# Motorsteuerung_V4.net
KiCad netlist of a schematic drawn in Altium Designer
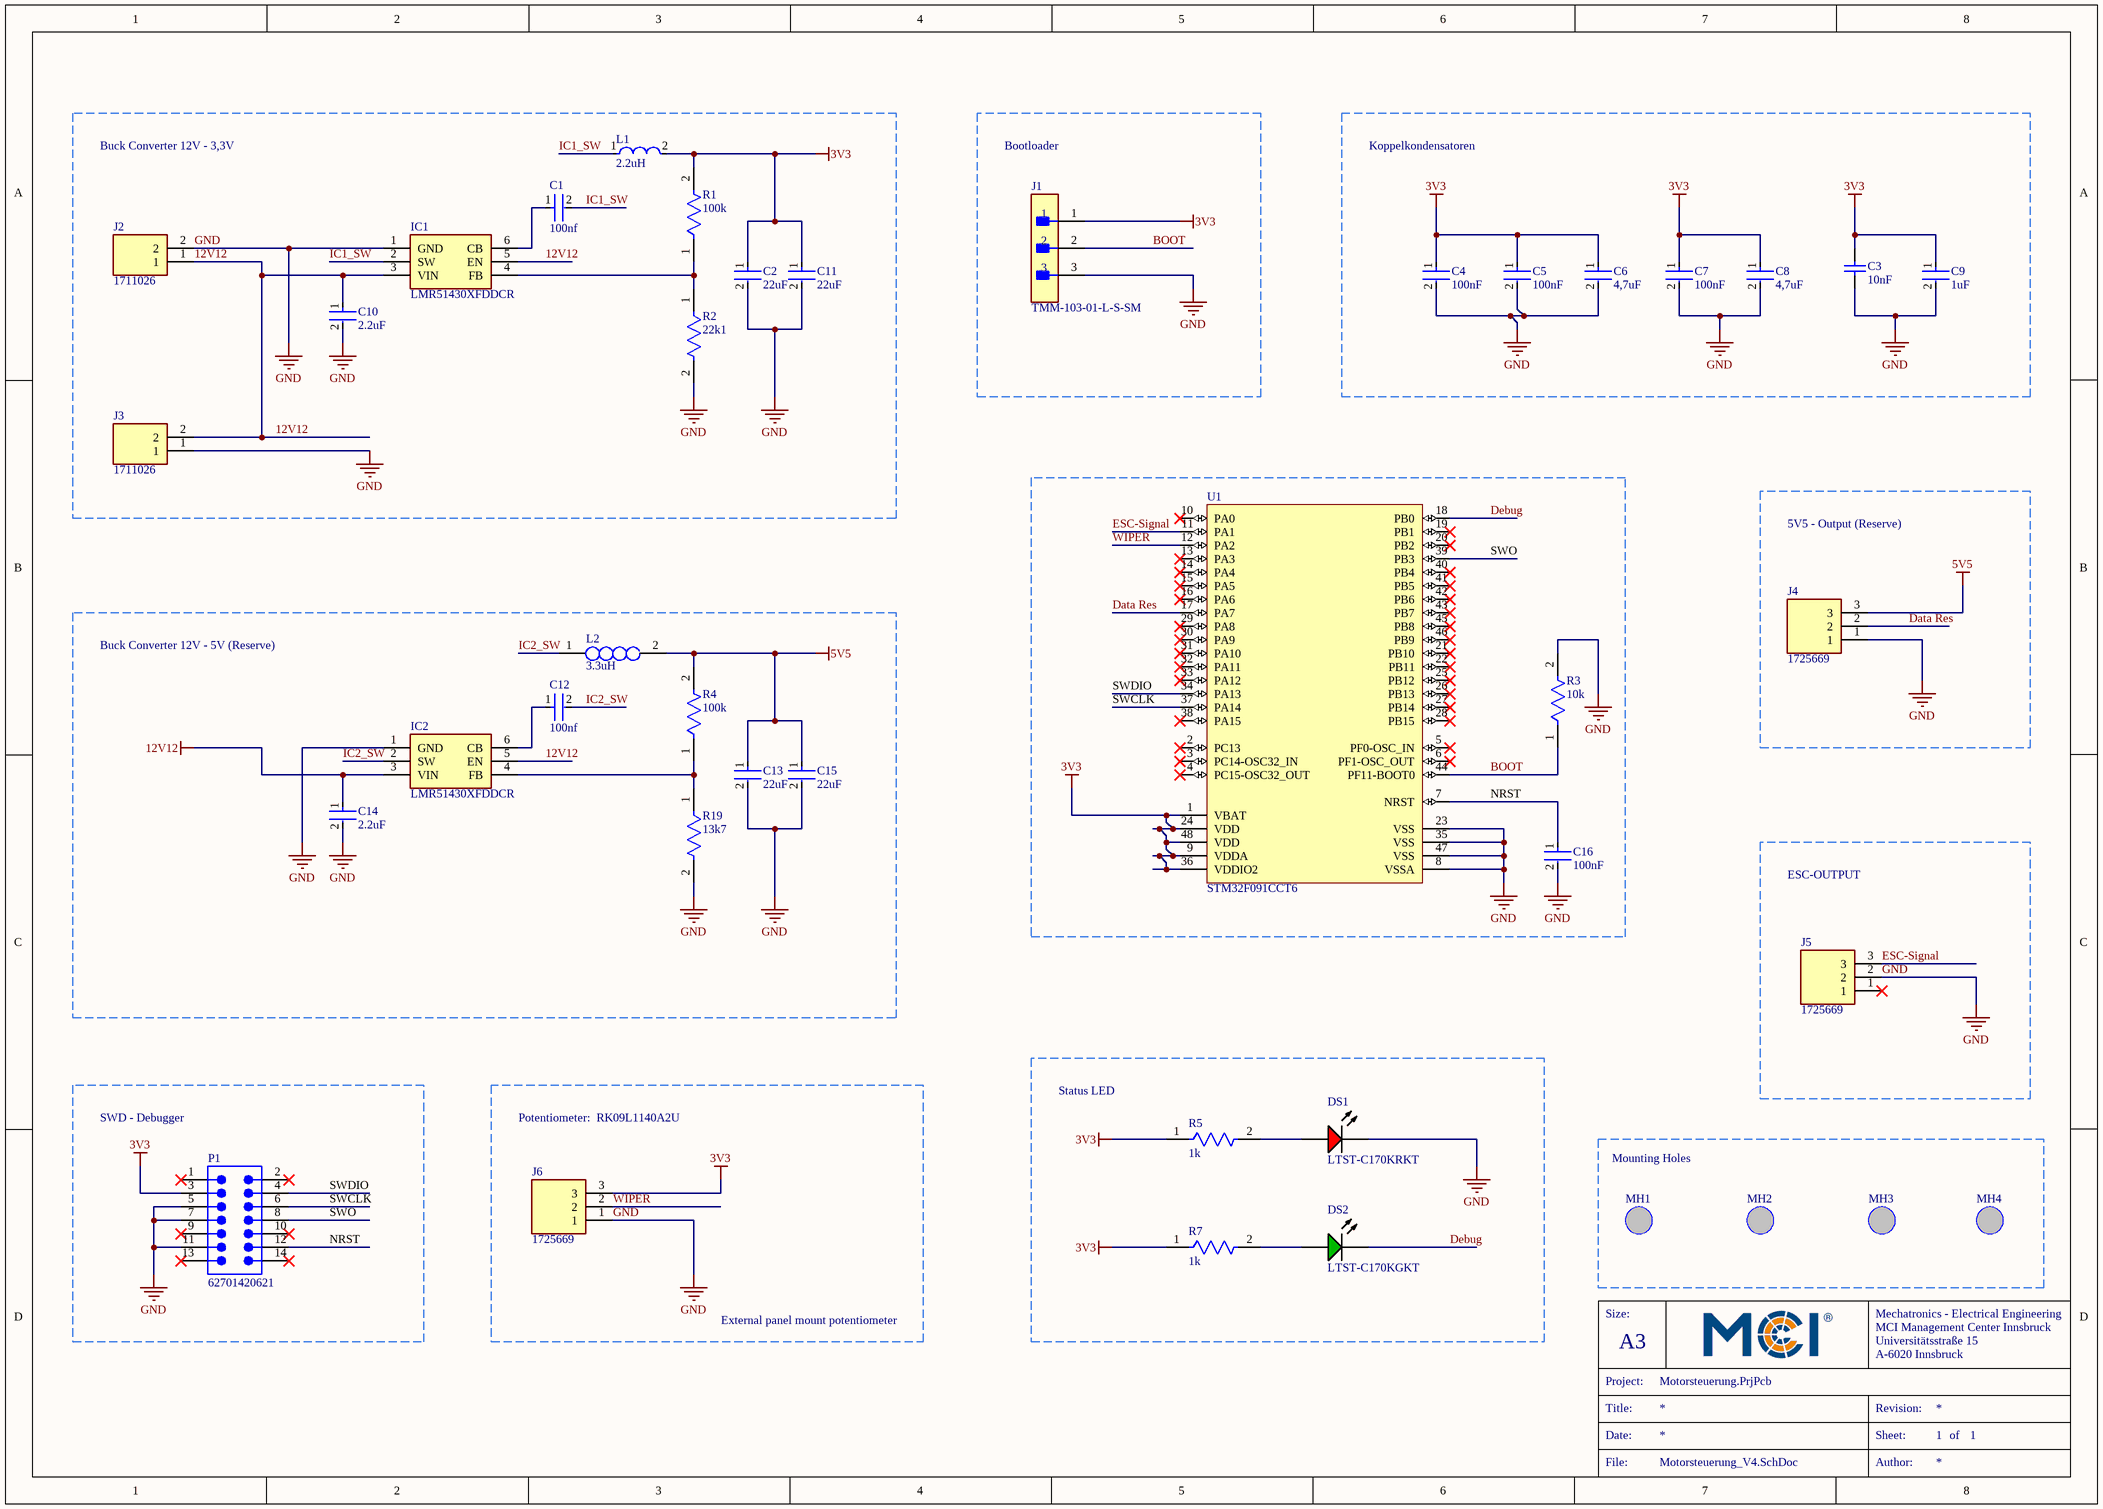
[diagram p0: Motorsteuerung_V4.SchDoc]

(export (version "E")
  (design (tool "Eeschema 10.0.6"))
  (components
    (comp (ref "C1")
      (value "100nf")
      (footprint "FP-C0805C104M5UACTU-MFG")
      (description "CAP CER 0.1UF 50V Z5U 0805")
      (fields (field (name "TOLERANCE") "20%") (field (name "VOLTAGE") "50V"))
      (libsource (lib "Altium Content Vault") (part "b4654b650e69147ec39a6b967a45e02"))
    )
    (comp (ref "C2")
      (value "22uF")
      (footprint "FP-C1210C226K4RACTU-MFG")
      (description "CAP CER 22UF 16V X7R 1210")
      (fields (field (name "VOLTAGE") "16V") (field (name "TOLERANCE") "10%"))
      (libsource (lib "Altium Content Vault") (part "b4654b650e69147ec39a6b967a45e02"))
    )
    (comp (ref "C3")
      (value "10nF")
      (footprint "CAPC1608X92X38ML15T08")
      (fields (field (name "MANUFACTURER") "Vitramon") (field (name "PART NUMBER") "VJ0603Y103KXJAC"))
      (libsource (lib "Altium Content Vault") (part "CAP"))
    )
    (comp (ref "C4")
      (value "100nF")
      (footprint "FP-CC0603-DA-MFG")
      (description "CAP CER 0.1UF 25V X7R 0603")
      (fields
        (field (name "MANUFACTURER") "YAGEO")
        (field (name "OCTOPART") "https://octopart.com/cc0603krx7r8bb104-yageo-8376534")
      )
      (libsource (lib "Altium Content Vault") (part "11868f565c42a9108669ba33697ecf6"))
    )
    (comp (ref "C5")
      (value "100nF")
      (footprint "FP-CC0603-DA-MFG")
      (description "CAP CER 0.1UF 25V X7R 0603")
      (fields
        (field (name "MANUFACTURER") "YAGEO")
        (field (name "OCTOPART") "https://octopart.com/cc0603krx7r8bb104-yageo-8376534")
      )
      (libsource (lib "Altium Content Vault") (part "11868f565c42a9108669ba33697ecf6"))
    )
    (comp (ref "C6")
      (value "4,7uF")
      (footprint "FP-CC0603-DA-MFG")
      (description "CAP CER 4.7UF 16V X5R 0603")
      (fields
        (field (name "MANUFACTURER") "YAGEO")
        (field (name "MANUFACTURER PART NUMBER") "CC0603KRX5R7BB475")
      )
      (libsource (lib "Altium Content Vault") (part "11868f565c42a9108669ba33697ecf6"))
    )
    (comp (ref "C7")
      (value "100nF")
      (footprint "FP-CC0603-DA-MFG")
      (description "CAP CER 0.1UF 25V X7R 0603")
      (fields
        (field (name "MANUFACTURER") "YAGEO")
        (field (name "OCTOPART") "https://octopart.com/cc0603krx7r8bb104-yageo-8376534")
      )
      (libsource (lib "Altium Content Vault") (part "11868f565c42a9108669ba33697ecf6"))
    )
    (comp (ref "C8")
      (value "4,7uF")
      (footprint "FP-CC0603-DA-MFG")
      (description "CAP CER 4.7UF 16V X5R 0603")
      (fields
        (field (name "MANUFACTURER") "YAGEO")
        (field (name "MANUFACTURER PART NUMBER") "CC0603KRX5R7BB475")
      )
      (libsource (lib "Altium Content Vault") (part "11868f565c42a9108669ba33697ecf6"))
    )
    (comp (ref "C9")
      (value "1uF")
      (footprint "FP-CC0603-DA-MFG")
      (description "CAP CER 1UF 16V X5R 0603")
      (fields
        (field (name "OCTOPART") "https://octopart.com/cc0603krx5r7bb105-yageo-8376530")
        (field (name "MANUFACTURER PART NUMBER") "CC0603KRX5R7BB105")
      )
      (libsource (lib "Altium Content Vault") (part "11868f565c42a9108669ba33697ecf6"))
    )
    (comp (ref "C10")
      (value "2.2uF")
      (footprint "FP-CC1210-G3-MFG")
      (description "CAP CER 1210")
      (fields (field (name "TOLERANCE") "10%"))
      (libsource (lib "Altium Content Vault") (part "b4654b650e69147ec39a6b967a45e02"))
    )
    (comp (ref "C11")
      (value "22uF")
      (footprint "FP-C1210C226K4RACTU-MFG")
      (description "CAP CER 22UF 16V X7R 1210")
      (fields (field (name "VOLTAGE") "16V") (field (name "TOLERANCE") "10%"))
      (libsource (lib "Altium Content Vault") (part "b4654b650e69147ec39a6b967a45e02"))
    )
    (comp (ref "C12")
      (value "100nf")
      (footprint "FP-C0805C104M5UACTU-MFG")
      (description "CAP CER 0.1UF 50V Z5U 0805")
      (fields (field (name "TOLERANCE") "20%") (field (name "VOLTAGE") "50V"))
      (libsource (lib "Altium Content Vault") (part "b4654b650e69147ec39a6b967a45e02"))
    )
    (comp (ref "C13")
      (value "22uF")
      (footprint "FP-C1210C226K4RACTU-MFG")
      (description "CAP CER 22UF 16V X7R 1210")
      (fields (field (name "VOLTAGE") "16V") (field (name "TOLERANCE") "10%"))
      (libsource (lib "Altium Content Vault") (part "b4654b650e69147ec39a6b967a45e02"))
    )
    (comp (ref "C14")
      (value "2.2uF")
      (footprint "FP-CC1210-G3-MFG")
      (description "CAP CER 1210")
      (fields (field (name "TOLERANCE") "10%"))
      (libsource (lib "Altium Content Vault") (part "b4654b650e69147ec39a6b967a45e02"))
    )
    (comp (ref "C15")
      (value "22uF")
      (footprint "FP-C1210C226K4RACTU-MFG")
      (description "CAP CER 22UF 16V X7R 1210")
      (fields (field (name "VOLTAGE") "16V") (field (name "TOLERANCE") "10%"))
      (libsource (lib "Altium Content Vault") (part "b4654b650e69147ec39a6b967a45e02"))
    )
    (comp (ref "C16")
      (value "100nF")
      (footprint "FP-CC0805-EB-MFG")
      (description "CC0805KKX7RYBB104 Capacitor Ceramic 0.01uF 250V X7R 10% 0805 T/R")
      (fields (field (name "TOLERANCE") "10%"))
      (libsource (lib "Altium Content Vault") (part "b4654b650e69147ec39a6b967a45e02"))
    )
    (comp (ref "DS1")
      (value "LTST-C170KRKT")
      (footprint "LTST-C170KRKT_V")
      (description "LED Red, 75 mW, 54 mcd, -55 to 85 degC, 2-Pin SMD, RoHS, Tape and Reel")
      (fields (field (name "MANUFACTURER") "Lite-On"))
      (libsource (lib "Altium Content Vault") (part "LED-RED-AK-2"))
    )
    (comp (ref "DS2")
      (value "LTST-C170KGKT")
      (footprint "LTST-LTST-C170KGKT-2_V")
      (description "Ultra Bright AlInGaP Chip LED, 75 mW, -55 to 85 degC, 2-Pin SMD (0805), RoHS, Tape and Reel")
      (fields (field (name "MANUFACTURER") "Lite-On"))
      (libsource (lib "Altium Content Vault") (part "LED-GREEN-KA-2"))
    )
    (comp (ref "IC1")
      (value "LMR51430XFDDCR")
      (footprint "SamacSys:SOT95P280X110-6N")
      (description "Integrated Circuit")
      (fields (field (name "MOUSER PART NUMBER") "595-LMR51430XFDDCR"))
      (libsource (lib "*") (part "LMR51430XFDDCR"))
    )
    (comp (ref "IC2")
      (value "LMR51430XFDDCR")
      (footprint "SamacSys:SOT95P280X110-6N")
      (description "Integrated Circuit")
      (fields (field (name "MOUSER PART NUMBER") "595-LMR51430XFDDCR"))
      (libsource (lib "*") (part "LMR51430XFDDCR"))
    )
    (comp (ref "J1")
      (value "TMM-103-01-L-S-SM")
      (footprint "FP-TMM-103-01-L-S-SM-MFG")
      (description "CONN HEADER SMD 3POS 2MM")
      (libsource (lib "Altium Content Vault") (part "0d3f023dd272f625e17a2be33dea85f"))
    )
    (comp (ref "J2")
      (value "1711026")
      (footprint "SamacSys:1711026")
      (description "Connector")
      (fields (field (name "MOUSER PART NUMBER") "651-1711026"))
      (libsource (lib "*") (part "1711026"))
    )
    (comp (ref "J3")
      (value "1711026")
      (footprint "SamacSys:1711026")
      (description "Connector")
      (fields (field (name "MOUSER PART NUMBER") "651-1711026"))
      (libsource (lib "*") (part "1711026"))
    )
    (comp (ref "J4")
      (value "1725669")
      (footprint "SamacSys:1725669")
      (description "Connector")
      (fields (field (name "MOUSER PART NUMBER") "651-1725669"))
      (libsource (lib "*") (part "1725669"))
    )
    (comp (ref "J5")
      (value "1725669")
      (footprint "SamacSys:1725669")
      (description "Connector")
      (fields (field (name "MOUSER PART NUMBER") "651-1725669"))
      (libsource (lib "*") (part "1725669"))
    )
    (comp (ref "J6")
      (value "1725669")
      (footprint "SamacSys:1725669")
      (description "Connector")
      (fields (field (name "MOUSER PART NUMBER") "651-1725669"))
      (libsource (lib "*") (part "1725669"))
    )
    (comp (ref "L1")
      (value "2.2uH")
      (footprint "FP-IHLP-2020BZ-FP_1_905x2-MFG")
      (description "Fixed Inductors Commercial Low DCR Series 2.2uH 5A 37.7mΩ 20%")
      (fields (field (name "TOLERANCE") "20%"))
      (libsource (lib "Altium Content Vault") (part "725321dda6339637d4d059423bc1c3c"))
    )
    (comp (ref "L2")
      (value "3.3uH")
      (footprint "SamacSys:INDPM6054X300N")
      (description "Inductor")
      (fields
        (field (name "MANUFACTURER_PART_NUMBER") "PA4340.332NLT")
        (field (name "MOUSER PART NUMBER") "673-PA4340.332NLT")
      )
      (libsource (lib "*") (part "PA4340.332NLT"))
    )
    (comp (ref "MH1") (value "~") (footprint "MTH") (libsource (lib "MTH") (part "MountingHole")))
    (comp (ref "MH2") (value "~") (footprint "MTH") (libsource (lib "MTH") (part "MountingHole")))
    (comp (ref "MH3") (value "~") (footprint "MTH") (libsource (lib "MTH") (part "MountingHole")))
    (comp (ref "MH4") (value "~") (footprint "MTH") (libsource (lib "MTH") (part "MountingHole")))
    (comp (ref "P1")
      (value "62701420621")
      (footprint "62701420621")
      (description "Conn, Hdr, 14Pos, 2Row, 1.27Mm, Smt Rohs Compliant: Yes")
      (libsource (lib "Altium Content Vault") (part "Header_Male_2R_14P"))
    )
    (comp (ref "R1")
      (value "100k")
      (footprint "FP-RQ73C2A-IPC_B")
      (description "RQ73 0805 100KΩ 0.2W 10ppm/°C 0.1% 100V")
      (libsource (lib "Altium Content Vault") (part "1029c3af85768c4190bb7ad29bc67b5"))
    )
    (comp (ref "R2")
      (value "22k1")
      (footprint "FP-RT0805-MFG")
      (description "RES SMD 22.1K OHM 0.1% 1/8W 0805")
      (fields
        (field (name "MANUFACTURER PART NUMBER") "RT0805BRD0722K1L")
        (field (name "MANUFACTURER") "Yageo")
      )
      (libsource (lib "Altium Content Vault") (part "1029c3af85768c4190bb7ad29bc67b5"))
    )
    (comp (ref "R3")
      (value "10k")
      (footprint "FP-AT0805-MFG")
      (description "Thin Film Chip Resistors Automotive Grade 10kΩ 0.5% 50ppm/°C 0805")
      (fields (field (name "TOLERANCE") "0.5%"))
      (libsource (lib "Altium Content Vault") (part "1029c3af85768c4190bb7ad29bc67b5"))
    )
    (comp (ref "R4")
      (value "100k")
      (footprint "FP-RQ73C2A-IPC_B")
      (description "RQ73 0805 100KΩ 0.2W 10ppm/°C 0.1% 100V")
      (libsource (lib "Altium Content Vault") (part "1029c3af85768c4190bb7ad29bc67b5"))
    )
    (comp (ref "R5")
      (value "1k")
      (footprint "FP-AT0805-IPC_C")
      (description "Thin Film Chip Resistors Automotive Grade 1kΩ 0.1% 50ppm/°C 0805")
      (libsource (lib "Altium Content Vault") (part "1029c3af85768c4190bb7ad29bc67b5"))
    )
    (comp (ref "R7")
      (value "1k")
      (footprint "FP-AT0805-IPC_C")
      (description "Thin Film Chip Resistors Automotive Grade 1kΩ 0.1% 50ppm/°C 0805")
      (libsource (lib "Altium Content Vault") (part "1029c3af85768c4190bb7ad29bc67b5"))
    )
    (comp (ref "R19")
      (value "13k7")
      (footprint "FP-RT0805-MFG")
      (description "RES 13.7K OHM 1/8W .1% SMD 0805")
      (fields
        (field (name "MANUFACTURER PART NUMBER") "RT0805BRD0713K7L")
        (field (name "MANUFACTURER") "Yageo")
      )
      (libsource (lib "Altium Content Vault") (part "1029c3af85768c4190bb7ad29bc67b5"))
    )
    (comp (ref "U1")
      (value "STM32F091CCT6")
      (footprint "LQFP48_M")
      (fields (field (name "MANUFACTURER") "STMicroelectronics"))
      (libsource (lib "Altium Content Vault") (part "STM-STM32F091C-LQFP-48"))
    )
  )
  (nets
    (net (code "1") (name "/BOOT") (class "Default")
      (node (ref "J1") (pin "2") (pinfunction "2_2") (pintype "passive"))
      (node (ref "R3") (pin "1") (pinfunction "1_1") (pintype "passive"))
      (node (ref "U1") (pin "44") (pinfunction "PF11-BOOT0_44") (pintype "bidirectional"))
    )
    (net (code "2") (name "/Data Res") (class "Default")
      (node (ref "J4") (pin "2") (pinfunction "2_2") (pintype "passive"))
      (node (ref "U1") (pin "17") (pinfunction "PA7_17") (pintype "bidirectional"))
    )
    (net (code "3") (name "/Debug") (class "Default")
      (node (ref "DS2") (pin "1") (pinfunction "K_1") (pintype "passive"))
      (node (ref "U1") (pin "18") (pinfunction "PB0_18") (pintype "bidirectional"))
    )
    (net (code "4") (name "/ESC-Signal") (class "Default")
      (node (ref "J5") (pin "3") (pinfunction "3_3") (pintype "passive"))
      (node (ref "U1") (pin "11") (pinfunction "PA1_11") (pintype "bidirectional"))
    )
    (net (code "5") (name "/IC1_SW") (class "Default")
      (node (ref "C1") (pin "2") (pinfunction "2_2") (pintype "passive"))
      (node (ref "IC1") (pin "2") (pinfunction "SW_2") (pintype "passive"))
      (node (ref "L1") (pin "1") (pinfunction "1_1") (pintype "passive"))
    )
    (net (code "6") (name "/IC2_SW") (class "Default")
      (node (ref "C12") (pin "2") (pinfunction "2_2") (pintype "passive"))
      (node (ref "IC2") (pin "2") (pinfunction "SW_2") (pintype "passive"))
      (node (ref "L2") (pin "1") (pinfunction "1_1") (pintype "passive"))
    )
    (net (code "7") (name "/NRST") (class "Default")
      (node (ref "C16") (pin "1") (pinfunction "1_1") (pintype "passive"))
      (node (ref "P1") (pin "12") (pinfunction "12_12") (pintype "passive"))
      (node (ref "U1") (pin "7") (pinfunction "NRST_7") (pintype "bidirectional"))
    )
    (net (code "8") (name "/SWCLK") (class "Default")
      (node (ref "P1") (pin "6") (pinfunction "6_6") (pintype "passive"))
      (node (ref "U1") (pin "37") (pinfunction "PA14_37") (pintype "bidirectional"))
    )
    (net (code "9") (name "/SWDIO") (class "Default")
      (node (ref "P1") (pin "4") (pinfunction "4_4") (pintype "passive"))
      (node (ref "U1") (pin "34") (pinfunction "PA13_34") (pintype "bidirectional"))
    )
    (net (code "10") (name "/SWO") (class "Default")
      (node (ref "P1") (pin "8") (pinfunction "8_8") (pintype "passive"))
      (node (ref "U1") (pin "39") (pinfunction "PB3_39") (pintype "bidirectional"))
    )
    (net (code "11") (name "/WIPER") (class "Default")
      (node (ref "J6") (pin "2") (pinfunction "2_2") (pintype "passive"))
      (node (ref "U1") (pin "12") (pinfunction "PA2_12") (pintype "bidirectional"))
    )
    (net (code "12") (name "3V3") (class "Default")
      (node (ref "C11") (pin "1") (pinfunction "1_1") (pintype "passive"))
      (node (ref "C2") (pin "1") (pinfunction "1_1") (pintype "passive"))
      (node (ref "C3") (pin "2") (pinfunction "2_2") (pintype "passive"))
      (node (ref "C4") (pin "1") (pinfunction "1_1") (pintype "passive"))
      (node (ref "C5") (pin "1") (pinfunction "1_1") (pintype "passive"))
      (node (ref "C6") (pin "1") (pinfunction "1_1") (pintype "passive"))
      (node (ref "C7") (pin "1") (pinfunction "1_1") (pintype "passive"))
      (node (ref "C8") (pin "1") (pinfunction "1_1") (pintype "passive"))
      (node (ref "C9") (pin "1") (pinfunction "1_1") (pintype "passive"))
      (node (ref "J1") (pin "1") (pinfunction "1_1") (pintype "passive"))
      (node (ref "J6") (pin "3") (pinfunction "3_3") (pintype "passive"))
      (node (ref "L1") (pin "2") (pinfunction "2_2") (pintype "passive"))
      (node (ref "P1") (pin "3") (pinfunction "3_3") (pintype "passive"))
      (node (ref "R1") (pin "2") (pinfunction "2_2") (pintype "passive"))
      (node (ref "R5") (pin "1") (pinfunction "1_1") (pintype "passive"))
      (node (ref "R7") (pin "1") (pinfunction "1_1") (pintype "passive"))
      (node (ref "U1") (pin "1") (pinfunction "VBAT_1") (pintype "power_in"))
      (node (ref "U1") (pin "24") (pinfunction "VDD_24") (pintype "power_in"))
      (node (ref "U1") (pin "36") (pinfunction "VDDIO2_36") (pintype "power_in"))
      (node (ref "U1") (pin "48") (pinfunction "VDD_48") (pintype "power_in"))
      (node (ref "U1") (pin "9") (pinfunction "VDDA_9") (pintype "power_in"))
    )
    (net (code "13") (name "5V5") (class "Default")
      (node (ref "C13") (pin "1") (pinfunction "1_1") (pintype "passive"))
      (node (ref "C15") (pin "1") (pinfunction "1_1") (pintype "passive"))
      (node (ref "J4") (pin "3") (pinfunction "3_3") (pintype "passive"))
      (node (ref "L2") (pin "2") (pinfunction "2_2") (pintype "passive"))
      (node (ref "R4") (pin "2") (pinfunction "2_2") (pintype "passive"))
    )
    (net (code "14") (name "12V12") (class "Default")
      (node (ref "C10") (pin "1") (pinfunction "1_1") (pintype "passive"))
      (node (ref "C14") (pin "1") (pinfunction "1_1") (pintype "passive"))
      (node (ref "IC1") (pin "3") (pinfunction "VIN_3") (pintype "passive"))
      (node (ref "IC1") (pin "5") (pinfunction "EN_5") (pintype "passive"))
      (node (ref "IC2") (pin "3") (pinfunction "VIN_3") (pintype "passive"))
      (node (ref "IC2") (pin "5") (pinfunction "EN_5") (pintype "passive"))
      (node (ref "J2") (pin "1") (pinfunction "1_1") (pintype "passive"))
      (node (ref "J3") (pin "2") (pinfunction "2_2") (pintype "passive"))
    )
    (net (code "15") (name "GND") (class "Default")
      (node (ref "C10") (pin "2") (pinfunction "2_2") (pintype "passive"))
      (node (ref "C11") (pin "2") (pinfunction "2_2") (pintype "passive"))
      (node (ref "C13") (pin "2") (pinfunction "2_2") (pintype "passive"))
      (node (ref "C14") (pin "2") (pinfunction "2_2") (pintype "passive"))
      (node (ref "C15") (pin "2") (pinfunction "2_2") (pintype "passive"))
      (node (ref "C16") (pin "2") (pinfunction "2_2") (pintype "passive"))
      (node (ref "C2") (pin "2") (pinfunction "2_2") (pintype "passive"))
      (node (ref "C3") (pin "1") (pinfunction "1_1") (pintype "passive"))
      (node (ref "C4") (pin "2") (pinfunction "2_2") (pintype "passive"))
      (node (ref "C5") (pin "2") (pinfunction "2_2") (pintype "passive"))
      (node (ref "C6") (pin "2") (pinfunction "2_2") (pintype "passive"))
      (node (ref "C7") (pin "2") (pinfunction "2_2") (pintype "passive"))
      (node (ref "C8") (pin "2") (pinfunction "2_2") (pintype "passive"))
      (node (ref "C9") (pin "2") (pinfunction "2_2") (pintype "passive"))
      (node (ref "DS1") (pin "2") (pinfunction "K_2") (pintype "passive"))
      (node (ref "IC1") (pin "1") (pinfunction "GND_1") (pintype "passive"))
      (node (ref "IC2") (pin "1") (pinfunction "GND_1") (pintype "passive"))
      (node (ref "J1") (pin "3") (pinfunction "3_3") (pintype "passive"))
      (node (ref "J2") (pin "2") (pinfunction "2_2") (pintype "passive"))
      (node (ref "J3") (pin "1") (pinfunction "1_1") (pintype "passive"))
      (node (ref "J4") (pin "1") (pinfunction "1_1") (pintype "passive"))
      (node (ref "J5") (pin "2") (pinfunction "2_2") (pintype "passive"))
      (node (ref "J6") (pin "1") (pinfunction "1_1") (pintype "passive"))
      (node (ref "P1") (pin "11") (pinfunction "11_11") (pintype "passive"))
      (node (ref "P1") (pin "5") (pinfunction "5_5") (pintype "passive"))
      (node (ref "P1") (pin "7") (pinfunction "7_7") (pintype "passive"))
      (node (ref "R19") (pin "2") (pinfunction "2_2") (pintype "passive"))
      (node (ref "R2") (pin "2") (pinfunction "2_2") (pintype "passive"))
      (node (ref "R3") (pin "2") (pinfunction "2_2") (pintype "passive"))
      (node (ref "U1") (pin "23") (pinfunction "VSS_23") (pintype "power_in"))
      (node (ref "U1") (pin "35") (pinfunction "VSS_35") (pintype "power_in"))
      (node (ref "U1") (pin "47") (pinfunction "VSS_47") (pintype "power_in"))
      (node (ref "U1") (pin "8") (pinfunction "VSSA_8") (pintype "power_in"))
    )
    (net (code "16") (name "Net-(DS1-A)") (class "Default")
      (node (ref "DS1") (pin "1") (pinfunction "A_1") (pintype "passive"))
      (node (ref "R5") (pin "2") (pinfunction "2_2") (pintype "passive"))
    )
    (net (code "17") (name "Net-(DS2-A)") (class "Default")
      (node (ref "DS2") (pin "2") (pinfunction "A_2") (pintype "passive"))
      (node (ref "R7") (pin "2") (pinfunction "2_2") (pintype "passive"))
    )
    (net (code "18") (name "Net-(IC1-CB)") (class "Default")
      (node (ref "C1") (pin "1") (pinfunction "1_1") (pintype "passive"))
      (node (ref "IC1") (pin "6") (pinfunction "CB_6") (pintype "passive"))
    )
    (net (code "19") (name "Net-(IC1-FB)") (class "Default")
      (node (ref "IC1") (pin "4") (pinfunction "FB_4") (pintype "passive"))
      (node (ref "R1") (pin "1") (pinfunction "1_1") (pintype "passive"))
      (node (ref "R2") (pin "1") (pinfunction "1_1") (pintype "passive"))
    )
    (net (code "20") (name "Net-(IC2-CB)") (class "Default")
      (node (ref "C12") (pin "1") (pinfunction "1_1") (pintype "passive"))
      (node (ref "IC2") (pin "6") (pinfunction "CB_6") (pintype "passive"))
    )
    (net (code "21") (name "Net-(IC2-FB)") (class "Default")
      (node (ref "IC2") (pin "4") (pinfunction "FB_4") (pintype "passive"))
      (node (ref "R19") (pin "1") (pinfunction "1_1") (pintype "passive"))
      (node (ref "R4") (pin "1") (pinfunction "1_1") (pintype "passive"))
    )
    (net (code "22") (name "unconnected-(J5-Pad1)") (class "Default")
      (node (ref "J5") (pin "1") (pinfunction "1_1") (pintype "passive+no_connect"))
    )
    (net (code "23") (name "unconnected-(P1-Pad1)") (class "Default")
      (node (ref "P1") (pin "1") (pinfunction "1_1") (pintype "passive+no_connect"))
    )
    (net (code "24") (name "unconnected-(P1-Pad2)") (class "Default")
      (node (ref "P1") (pin "2") (pinfunction "2_2") (pintype "passive+no_connect"))
    )
    (net (code "25") (name "unconnected-(P1-Pad9)") (class "Default")
      (node (ref "P1") (pin "9") (pinfunction "9_9") (pintype "passive+no_connect"))
    )
    (net (code "26") (name "unconnected-(P1-Pad10)") (class "Default")
      (node (ref "P1") (pin "10") (pinfunction "10_10") (pintype "passive+no_connect"))
    )
    (net (code "27") (name "unconnected-(P1-Pad13)") (class "Default")
      (node (ref "P1") (pin "13") (pinfunction "13_13") (pintype "passive+no_connect"))
    )
    (net (code "28") (name "unconnected-(P1-Pad14)") (class "Default")
      (node (ref "P1") (pin "14") (pinfunction "14_14") (pintype "passive+no_connect"))
    )
    (net (code "29") (name "unconnected-(U1-PA0-Pad10)") (class "Default")
      (node (ref "U1") (pin "10") (pinfunction "PA0_10") (pintype "bidirectional+no_connect"))
    )
    (net (code "30") (name "unconnected-(U1-PA3-Pad13)") (class "Default")
      (node (ref "U1") (pin "13") (pinfunction "PA3_13") (pintype "bidirectional+no_connect"))
    )
    (net (code "31") (name "unconnected-(U1-PA4-Pad14)") (class "Default")
      (node (ref "U1") (pin "14") (pinfunction "PA4_14") (pintype "bidirectional+no_connect"))
    )
    (net (code "32") (name "unconnected-(U1-PA5-Pad15)") (class "Default")
      (node (ref "U1") (pin "15") (pinfunction "PA5_15") (pintype "bidirectional+no_connect"))
    )
    (net (code "33") (name "unconnected-(U1-PA6-Pad16)") (class "Default")
      (node (ref "U1") (pin "16") (pinfunction "PA6_16") (pintype "bidirectional+no_connect"))
    )
    (net (code "34") (name "unconnected-(U1-PA8-Pad29)") (class "Default")
      (node (ref "U1") (pin "29") (pinfunction "PA8_29") (pintype "bidirectional+no_connect"))
    )
    (net (code "35") (name "unconnected-(U1-PA9-Pad30)") (class "Default")
      (node (ref "U1") (pin "30") (pinfunction "PA9_30") (pintype "bidirectional+no_connect"))
    )
    (net (code "36") (name "unconnected-(U1-PA10-Pad31)") (class "Default")
      (node (ref "U1") (pin "31") (pinfunction "PA10_31") (pintype "bidirectional+no_connect"))
    )
    (net (code "37") (name "unconnected-(U1-PA11-Pad32)") (class "Default")
      (node (ref "U1") (pin "32") (pinfunction "PA11_32") (pintype "bidirectional+no_connect"))
    )
    (net (code "38") (name "unconnected-(U1-PA12-Pad33)") (class "Default")
      (node (ref "U1") (pin "33") (pinfunction "PA12_33") (pintype "bidirectional+no_connect"))
    )
    (net (code "39") (name "unconnected-(U1-PA15-Pad38)") (class "Default")
      (node (ref "U1") (pin "38") (pinfunction "PA15_38") (pintype "bidirectional+no_connect"))
    )
    (net (code "40") (name "unconnected-(U1-PB1-Pad19)") (class "Default")
      (node (ref "U1") (pin "19") (pinfunction "PB1_19") (pintype "bidirectional+no_connect"))
    )
    (net (code "41") (name "unconnected-(U1-PB2-Pad20)") (class "Default")
      (node (ref "U1") (pin "20") (pinfunction "PB2_20") (pintype "bidirectional+no_connect"))
    )
    (net (code "42") (name "unconnected-(U1-PB4-Pad40)") (class "Default")
      (node (ref "U1") (pin "40") (pinfunction "PB4_40") (pintype "bidirectional+no_connect"))
    )
    (net (code "43") (name "unconnected-(U1-PB5-Pad41)") (class "Default")
      (node (ref "U1") (pin "41") (pinfunction "PB5_41") (pintype "bidirectional+no_connect"))
    )
    (net (code "44") (name "unconnected-(U1-PB6-Pad42)") (class "Default")
      (node (ref "U1") (pin "42") (pinfunction "PB6_42") (pintype "bidirectional+no_connect"))
    )
    (net (code "45") (name "unconnected-(U1-PB7-Pad43)") (class "Default")
      (node (ref "U1") (pin "43") (pinfunction "PB7_43") (pintype "bidirectional+no_connect"))
    )
    (net (code "46") (name "unconnected-(U1-PB8-Pad45)") (class "Default")
      (node (ref "U1") (pin "45") (pinfunction "PB8_45") (pintype "bidirectional+no_connect"))
    )
    (net (code "47") (name "unconnected-(U1-PB9-Pad46)") (class "Default")
      (node (ref "U1") (pin "46") (pinfunction "PB9_46") (pintype "bidirectional+no_connect"))
    )
    (net (code "48") (name "unconnected-(U1-PB10-Pad21)") (class "Default")
      (node (ref "U1") (pin "21") (pinfunction "PB10_21") (pintype "bidirectional+no_connect"))
    )
    (net (code "49") (name "unconnected-(U1-PB11-Pad22)") (class "Default")
      (node (ref "U1") (pin "22") (pinfunction "PB11_22") (pintype "bidirectional+no_connect"))
    )
    (net (code "50") (name "unconnected-(U1-PB12-Pad25)") (class "Default")
      (node (ref "U1") (pin "25") (pinfunction "PB12_25") (pintype "bidirectional+no_connect"))
    )
    (net (code "51") (name "unconnected-(U1-PB13-Pad26)") (class "Default")
      (node (ref "U1") (pin "26") (pinfunction "PB13_26") (pintype "bidirectional+no_connect"))
    )
    (net (code "52") (name "unconnected-(U1-PB14-Pad27)") (class "Default")
      (node (ref "U1") (pin "27") (pinfunction "PB14_27") (pintype "bidirectional+no_connect"))
    )
    (net (code "53") (name "unconnected-(U1-PB15-Pad28)") (class "Default")
      (node (ref "U1") (pin "28") (pinfunction "PB15_28") (pintype "bidirectional+no_connect"))
    )
    (net (code "54") (name "unconnected-(U1-PC13-Pad2)") (class "Default")
      (node (ref "U1") (pin "2") (pinfunction "PC13_2") (pintype "bidirectional+no_connect"))
    )
    (net (code "55") (name "unconnected-(U1-PC14-OSC32_IN-Pad3)") (class "Default")
      (node (ref "U1") (pin "3") (pinfunction "PC14-OSC32_IN_3") (pintype "bidirectional+no_connect"))
    )
    (net (code "56") (name "unconnected-(U1-PC15-OSC32_OUT-Pad4)") (class "Default")
      (node (ref "U1") (pin "4") (pinfunction "PC15-OSC32_OUT_4") (pintype "bidirectional+no_connect"))
    )
    (net (code "57") (name "unconnected-(U1-PF0-OSC_IN-Pad5)") (class "Default")
      (node (ref "U1") (pin "5") (pinfunction "PF0-OSC_IN_5") (pintype "bidirectional+no_connect"))
    )
    (net (code "58") (name "unconnected-(U1-PF1-OSC_OUT-Pad6)") (class "Default")
      (node (ref "U1") (pin "6") (pinfunction "PF1-OSC_OUT_6") (pintype "bidirectional+no_connect"))
    )
  )
)
